# connector_schematic.net
KiCad netlist of a schematic drawn in EAGLE
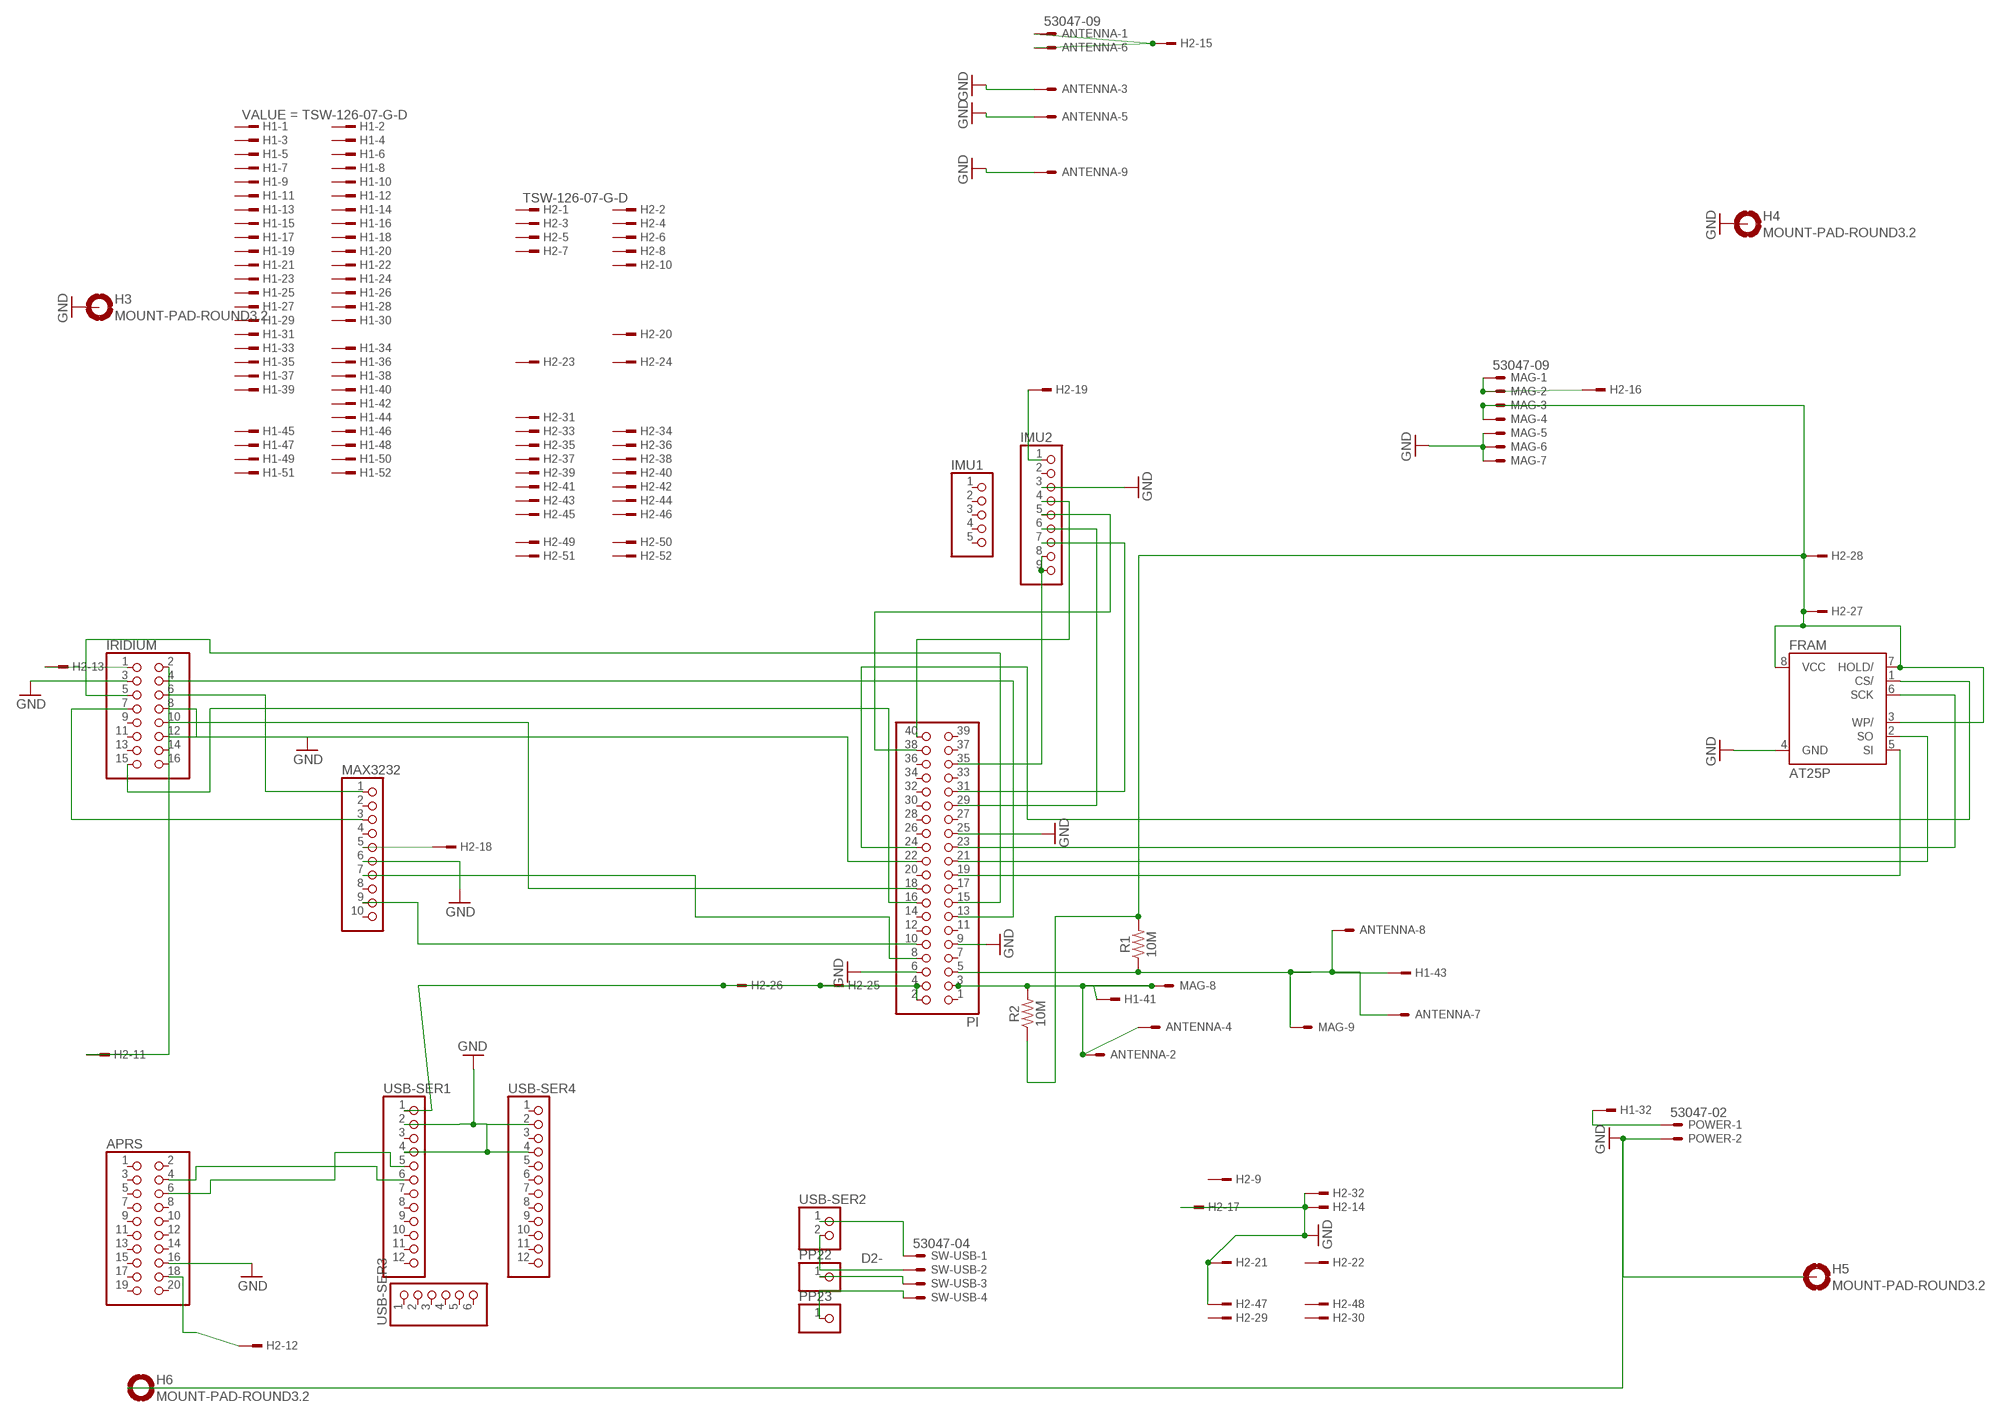
[diagram p0: schematic, sheet 1]

(export (version "E")
  (design (tool "Eeschema 10.0.6"))
  (components
    (comp (ref "ANTENNA")
      (value "53047-09")
      (footprint "eagle-import:53047-09")
      (fields (field (name "MF") "MOLEX") (field (name "MPN") "53047-0910"))
      (libsource (lib "eagle-import") (part "53?-09047"))
    )
    (comp (ref "APRS")
      (value "PINHD-2X10")
      (footprint "eagle-import:2X10")
      (libsource (lib "eagle-import") (part "PINHD-2X10"))
    )
    (comp (ref "FRAM")
      (value "AT25P")
      (footprint "eagle-import:DIL08")
      (fields (field (name "MPN") "CAT25040LI-G"))
      (libsource (lib "eagle-import") (part "AT25P"))
    )
    (comp (ref "H1")
      (value "TSW-126-07-G-D")
      (footprint "eagle-import:TSW-126-XX-G-D")
      (fields (field (name "MF") "Samtec Inc."))
      (libsource (lib "eagle-import") (part "TSW-126--G-D07"))
    )
    (comp (ref "H2")
      (value "TSW-126-07-G-D")
      (footprint "eagle-import:TSW-126-XX-G-D")
      (fields (field (name "MF") "Samtec Inc."))
      (libsource (lib "eagle-import") (part "TSW-126--G-D07"))
    )
    (comp (ref "H3")
      (value "MOUNT-PAD-ROUND3.2")
      (footprint "eagle-import:3,2-PAD")
      (libsource (lib "eagle-import") (part "MOUNT-PAD-ROUND3.2"))
    )
    (comp (ref "H4")
      (value "MOUNT-PAD-ROUND3.2")
      (footprint "eagle-import:3,2-PAD")
      (libsource (lib "eagle-import") (part "MOUNT-PAD-ROUND3.2"))
    )
    (comp (ref "H5")
      (value "MOUNT-PAD-ROUND3.2")
      (footprint "eagle-import:3,2-PAD")
      (libsource (lib "eagle-import") (part "MOUNT-PAD-ROUND3.2"))
    )
    (comp (ref "H6")
      (value "MOUNT-PAD-ROUND3.2")
      (footprint "eagle-import:3,2-PAD")
      (libsource (lib "eagle-import") (part "MOUNT-PAD-ROUND3.2"))
    )
    (comp (ref "IMU1")
      (value "PINHD-1X5")
      (footprint "eagle-import:1X05")
      (libsource (lib "eagle-import") (part "PINHD-1X5"))
    )
    (comp (ref "IMU2")
      (value "PINHD-1X9")
      (footprint "eagle-import:1X09")
      (libsource (lib "eagle-import") (part "PINHD-1X9"))
    )
    (comp (ref "IRIDIUM")
      (value "PINHD-2X8")
      (footprint "eagle-import:2X08")
      (libsource (lib "eagle-import") (part "PINHD-2X8"))
    )
    (comp (ref "MAG")
      (value "53047-09")
      (footprint "eagle-import:53047-09")
      (fields (field (name "MF") "MOLEX") (field (name "MPN") "53047-0910"))
      (libsource (lib "eagle-import") (part "53?-09047"))
    )
    (comp (ref "MAX3232")
      (value "PINHD-1X10")
      (footprint "eagle-import:1X10")
      (libsource (lib "eagle-import") (part "PINHD-1X10"))
    )
    (comp (ref "PI")
      (value "PINHD-2X20")
      (footprint "eagle-import:2X20")
      (libsource (lib "eagle-import") (part "PINHD-2X20"))
    )
    (comp (ref "POWER")
      (value "53047-02")
      (footprint "eagle-import:53047-02")
      (fields (field (name "MF") "MOLEX") (field (name "MPN") "53047-0210"))
      (libsource (lib "eagle-import") (part "53?-02047"))
    )
    (comp (ref "PP22")
      (value "PINHD-1X1")
      (footprint "eagle-import:1X01")
      (libsource (lib "eagle-import") (part "PINHD-1X1"))
    )
    (comp (ref "PP23")
      (value "PINHD-1X1")
      (footprint "eagle-import:1X01")
      (libsource (lib "eagle-import") (part "PINHD-1X1"))
    )
    (comp (ref "R1")
      (value "10M")
      (footprint "eagle-import:AXIAL-0.3")
      (libsource (lib "eagle-import") (part "10MOHM-HORIZ-1/4W-5%"))
    )
    (comp (ref "R2")
      (value "10M")
      (footprint "eagle-import:AXIAL-0.3")
      (libsource (lib "eagle-import") (part "10MOHM-HORIZ-1/4W-5%"))
    )
    (comp (ref "SW-USB")
      (value "53047-04")
      (footprint "eagle-import:53047-04")
      (fields (field (name "MF") "WALDOM/MOLEX") (field (name "MPN") "53047-0410"))
      (libsource (lib "eagle-import") (part "53?-04047"))
    )
    (comp (ref "USB-SER1")
      (value "PINHD-1X12")
      (footprint "eagle-import:1X12")
      (libsource (lib "eagle-import") (part "PINHD-1X12"))
    )
    (comp (ref "USB-SER2")
      (value "PINHD-1X2")
      (footprint "eagle-import:1X02")
      (libsource (lib "eagle-import") (part "PINHD-1X2"))
    )
    (comp (ref "USB-SER3")
      (value "PINHD-1X6")
      (footprint "eagle-import:1X06")
      (libsource (lib "eagle-import") (part "PINHD-1X6"))
    )
    (comp (ref "USB-SER4")
      (value "PINHD-1X12")
      (footprint "eagle-import:1X12")
      (libsource (lib "eagle-import") (part "PINHD-1X12"))
    )
  )
  (nets
    (net (code "1") (name "/D2-") (class "Default")
      (node (ref "SW-USB") (pin "2") (pinfunction "S_2") (pintype "passive"))
      (node (ref "USB-SER2") (pin "2") (pinfunction "2_2") (pintype "passive"))
    )
    (net (code "2") (name "GND") (class "Default")
      (node (ref "ANTENNA") (pin "3") (pinfunction "S_3") (pintype "passive"))
      (node (ref "ANTENNA") (pin "5") (pinfunction "S_5") (pintype "passive"))
      (node (ref "ANTENNA") (pin "9") (pinfunction "S_9") (pintype "passive"))
      (node (ref "APRS") (pin "16") (pinfunction "16_16") (pintype "passive"))
      (node (ref "FRAM") (pin "4") (pinfunction "GND_4") (pintype "power_in"))
      (node (ref "H2") (pin "14") (pinfunction "1_14") (pintype "passive"))
      (node (ref "H2") (pin "17") (pinfunction "1_17") (pintype "passive"))
      (node (ref "H2") (pin "21") (pinfunction "1_21") (pintype "passive"))
      (node (ref "H2") (pin "32") (pinfunction "1_32") (pintype "passive"))
      (node (ref "H2") (pin "47") (pinfunction "1_47") (pintype "passive"))
      (node (ref "H3") (pin "B3,2") (pinfunction "MOUNT_B3,2") (pintype "passive"))
      (node (ref "H4") (pin "B3,2") (pinfunction "MOUNT_B3,2") (pintype "passive"))
      (node (ref "H5") (pin "B3,2") (pinfunction "MOUNT_B3,2") (pintype "passive"))
      (node (ref "H6") (pin "B3,2") (pinfunction "MOUNT_B3,2") (pintype "passive"))
      (node (ref "IMU2") (pin "3") (pinfunction "3_3") (pintype "passive"))
      (node (ref "IRIDIUM") (pin "3") (pinfunction "3_3") (pintype "passive"))
      (node (ref "IRIDIUM") (pin "8") (pinfunction "8_8") (pintype "passive"))
      (node (ref "MAG") (pin "5") (pinfunction "S_5") (pintype "passive"))
      (node (ref "MAG") (pin "6") (pinfunction "S_6") (pintype "passive"))
      (node (ref "MAG") (pin "7") (pinfunction "S_7") (pintype "passive"))
      (node (ref "MAX3232") (pin "6") (pinfunction "6_6") (pintype "passive"))
      (node (ref "PI") (pin "25") (pinfunction "25_25") (pintype "passive"))
      (node (ref "PI") (pin "6") (pinfunction "6_6") (pintype "passive"))
      (node (ref "PI") (pin "9") (pinfunction "9_9") (pintype "passive"))
      (node (ref "POWER") (pin "2") (pinfunction "S_2") (pintype "passive"))
      (node (ref "USB-SER1") (pin "2") (pinfunction "2_2") (pintype "passive"))
      (node (ref "USB-SER1") (pin "4") (pinfunction "4_4") (pintype "passive"))
      (node (ref "USB-SER4") (pin "2") (pinfunction "2_2") (pintype "passive"))
      (node (ref "USB-SER4") (pin "4") (pinfunction "4_4") (pintype "passive"))
    )
    (net (code "3") (name "Net-(ANTENNAA-S)") (class "Default")
      (node (ref "ANTENNA") (pin "1") (pinfunction "S_1") (pintype "passive"))
      (node (ref "ANTENNA") (pin "6") (pinfunction "S_6") (pintype "passive"))
      (node (ref "H2") (pin "15") (pinfunction "1_15") (pintype "passive"))
    )
    (net (code "4") (name "Net-(ANTENNAB-S)") (class "Default")
      (node (ref "ANTENNA") (pin "2") (pinfunction "S_2") (pintype "passive"))
      (node (ref "ANTENNA") (pin "4") (pinfunction "S_4") (pintype "passive"))
      (node (ref "H1") (pin "41") (pinfunction "1_41") (pintype "passive"))
      (node (ref "MAG") (pin "8") (pinfunction "S_8") (pintype "passive"))
      (node (ref "PI") (pin "3") (pinfunction "3_3") (pintype "passive"))
      (node (ref "R2") (pin "P$2") (pinfunction "2_P$2") (pintype "passive"))
    )
    (net (code "5") (name "Net-(ANTENNAG-S)") (class "Default")
      (node (ref "ANTENNA") (pin "7") (pinfunction "S_7") (pintype "passive"))
      (node (ref "ANTENNA") (pin "8") (pinfunction "S_8") (pintype "passive"))
      (node (ref "H1") (pin "43") (pinfunction "1_43") (pintype "passive"))
      (node (ref "MAG") (pin "9") (pinfunction "S_9") (pintype "passive"))
      (node (ref "PI") (pin "5") (pinfunction "5_5") (pintype "passive"))
      (node (ref "R1") (pin "P$1") (pinfunction "1_P$1") (pintype "passive"))
    )
    (net (code "6") (name "Net-(APRS-Pad4)") (class "Default")
      (node (ref "APRS") (pin "4") (pinfunction "4_4") (pintype "passive"))
      (node (ref "USB-SER1") (pin "6") (pinfunction "6_6") (pintype "passive"))
    )
    (net (code "7") (name "Net-(APRS-Pad6)") (class "Default")
      (node (ref "APRS") (pin "6") (pinfunction "6_6") (pintype "passive"))
      (node (ref "USB-SER1") (pin "5") (pinfunction "5_5") (pintype "passive"))
    )
    (net (code "8") (name "Net-(FRAM-CS{slash})") (class "Default")
      (node (ref "FRAM") (pin "1") (pinfunction "CS/_1") (pintype "input"))
      (node (ref "PI") (pin "24") (pinfunction "24_24") (pintype "passive"))
    )
    (net (code "9") (name "Net-(FRAM-HOLD{slash})") (class "Default")
      (node (ref "FRAM") (pin "3") (pinfunction "WP/_3") (pintype "input"))
      (node (ref "FRAM") (pin "7") (pinfunction "HOLD/_7") (pintype "input"))
      (node (ref "FRAM") (pin "8") (pinfunction "VCC_8") (pintype "power_in"))
      (node (ref "H2") (pin "27") (pinfunction "1_27") (pintype "passive"))
      (node (ref "H2") (pin "28") (pinfunction "1_28") (pintype "passive"))
      (node (ref "MAG") (pin "3") (pinfunction "S_3") (pintype "passive"))
      (node (ref "MAG") (pin "4") (pinfunction "S_4") (pintype "passive"))
      (node (ref "R1") (pin "P$2") (pinfunction "2_P$2") (pintype "passive"))
      (node (ref "R2") (pin "P$1") (pinfunction "1_P$1") (pintype "passive"))
    )
    (net (code "10") (name "Net-(FRAM-SCK)") (class "Default")
      (node (ref "FRAM") (pin "6") (pinfunction "SCK_6") (pintype "bidirectional"))
      (node (ref "PI") (pin "23") (pinfunction "23_23") (pintype "passive"))
    )
    (net (code "11") (name "Net-(FRAM-SI)") (class "Default")
      (node (ref "FRAM") (pin "5") (pinfunction "SI_5") (pintype "bidirectional"))
      (node (ref "PI") (pin "19") (pinfunction "19_19") (pintype "passive"))
    )
    (net (code "12") (name "Net-(FRAM-SO)") (class "Default")
      (node (ref "FRAM") (pin "2") (pinfunction "SO_2") (pintype "input"))
      (node (ref "PI") (pin "21") (pinfunction "21_21") (pintype "passive"))
    )
    (net (code "13") (name "Net-(H1Z-1)") (class "Default")
      (node (ref "H1") (pin "32") (pinfunction "1_32") (pintype "passive"))
      (node (ref "POWER") (pin "1") (pinfunction "S_1") (pintype "passive"))
    )
    (net (code "14") (name "Net-(H2C-1)") (class "Default")
      (node (ref "H2") (pin "11") (pinfunction "1_11") (pintype "passive"))
      (node (ref "IRIDIUM") (pin "2") (pinfunction "2_2") (pintype "passive"))
    )
    (net (code "15") (name "Net-(H2D-1)") (class "Default")
      (node (ref "APRS") (pin "18") (pinfunction "18_18") (pintype "passive"))
      (node (ref "H2") (pin "12") (pinfunction "1_12") (pintype "passive"))
    )
    (net (code "16") (name "Net-(H2E-1)") (class "Default")
      (node (ref "H2") (pin "13") (pinfunction "1_13") (pintype "passive"))
      (node (ref "IRIDIUM") (pin "1") (pinfunction "1_1") (pintype "passive"))
    )
    (net (code "17") (name "Net-(H2H-1)") (class "Default")
      (node (ref "H2") (pin "16") (pinfunction "1_16") (pintype "passive"))
      (node (ref "MAG") (pin "1") (pinfunction "S_1") (pintype "passive"))
      (node (ref "MAG") (pin "2") (pinfunction "S_2") (pintype "passive"))
    )
    (net (code "18") (name "Net-(H2J-1)") (class "Default")
      (node (ref "H2") (pin "18") (pinfunction "1_18") (pintype "passive"))
      (node (ref "MAX3232") (pin "5") (pinfunction "5_5") (pintype "passive"))
    )
    (net (code "19") (name "Net-(H2K-1)") (class "Default")
      (node (ref "H2") (pin "19") (pinfunction "1_19") (pintype "passive"))
      (node (ref "IMU2") (pin "1") (pinfunction "1_1") (pintype "passive"))
    )
    (net (code "20") (name "Net-(H2R-1)") (class "Default")
      (node (ref "H2") (pin "25") (pinfunction "1_25") (pintype "passive"))
      (node (ref "H2") (pin "26") (pinfunction "1_26") (pintype "passive"))
      (node (ref "PI") (pin "2") (pinfunction "2_2") (pintype "passive"))
      (node (ref "PI") (pin "4") (pinfunction "4_4") (pintype "passive"))
      (node (ref "USB-SER1") (pin "1") (pinfunction "1_1") (pintype "passive"))
    )
    (net (code "21") (name "Net-(IMU2-Pad4)") (class "Default")
      (node (ref "IMU2") (pin "4") (pinfunction "4_4") (pintype "passive"))
      (node (ref "PI") (pin "40") (pinfunction "40_40") (pintype "passive"))
    )
    (net (code "22") (name "Net-(IMU2-Pad5)") (class "Default")
      (node (ref "IMU2") (pin "5") (pinfunction "5_5") (pintype "passive"))
      (node (ref "PI") (pin "38") (pinfunction "38_38") (pintype "passive"))
    )
    (net (code "23") (name "Net-(IMU2-Pad6)") (class "Default")
      (node (ref "IMU2") (pin "6") (pinfunction "6_6") (pintype "passive"))
      (node (ref "PI") (pin "29") (pinfunction "29_29") (pintype "passive"))
    )
    (net (code "24") (name "Net-(IMU2-Pad7)") (class "Default")
      (node (ref "IMU2") (pin "7") (pinfunction "7_7") (pintype "passive"))
      (node (ref "PI") (pin "31") (pinfunction "31_31") (pintype "passive"))
    )
    (net (code "25") (name "Net-(IMU2-Pad8)") (class "Default")
      (node (ref "IMU2") (pin "8") (pinfunction "8_8") (pintype "passive"))
      (node (ref "IMU2") (pin "9") (pinfunction "9_9") (pintype "passive"))
      (node (ref "PI") (pin "35") (pinfunction "35_35") (pintype "passive"))
    )
    (net (code "26") (name "Net-(IRIDIUM-Pad4)") (class "Default")
      (node (ref "IRIDIUM") (pin "4") (pinfunction "4_4") (pintype "passive"))
      (node (ref "PI") (pin "13") (pinfunction "13_13") (pintype "passive"))
    )
    (net (code "27") (name "Net-(IRIDIUM-Pad5)") (class "Default")
      (node (ref "IRIDIUM") (pin "5") (pinfunction "5_5") (pintype "passive"))
      (node (ref "PI") (pin "15") (pinfunction "15_15") (pintype "passive"))
    )
    (net (code "28") (name "Net-(IRIDIUM-Pad6)") (class "Default")
      (node (ref "IRIDIUM") (pin "6") (pinfunction "6_6") (pintype "passive"))
      (node (ref "MAX3232") (pin "1") (pinfunction "1_1") (pintype "passive"))
    )
    (net (code "29") (name "Net-(IRIDIUM-Pad7)") (class "Default")
      (node (ref "IRIDIUM") (pin "7") (pinfunction "7_7") (pintype "passive"))
      (node (ref "MAX3232") (pin "3") (pinfunction "3_3") (pintype "passive"))
    )
    (net (code "30") (name "Net-(IRIDIUM-Pad10)") (class "Default")
      (node (ref "IRIDIUM") (pin "10") (pinfunction "10_10") (pintype "passive"))
      (node (ref "PI") (pin "18") (pinfunction "18_18") (pintype "passive"))
    )
    (net (code "31") (name "Net-(IRIDIUM-Pad12)") (class "Default")
      (node (ref "IRIDIUM") (pin "12") (pinfunction "12_12") (pintype "passive"))
      (node (ref "PI") (pin "22") (pinfunction "22_22") (pintype "passive"))
    )
    (net (code "32") (name "Net-(IRIDIUM-Pad15)") (class "Default")
      (node (ref "IRIDIUM") (pin "15") (pinfunction "15_15") (pintype "passive"))
      (node (ref "PI") (pin "16") (pinfunction "16_16") (pintype "passive"))
    )
    (net (code "33") (name "Net-(MAX3232-Pad7)") (class "Default")
      (node (ref "MAX3232") (pin "7") (pinfunction "7_7") (pintype "passive"))
      (node (ref "PI") (pin "8") (pinfunction "8_8") (pintype "passive"))
    )
    (net (code "34") (name "Net-(MAX3232-Pad9)") (class "Default")
      (node (ref "MAX3232") (pin "9") (pinfunction "9_9") (pintype "passive"))
      (node (ref "PI") (pin "10") (pinfunction "10_10") (pintype "passive"))
    )
    (net (code "35") (name "Net-(SW-USBA-S)") (class "Default")
      (node (ref "SW-USB") (pin "1") (pinfunction "S_1") (pintype "passive"))
      (node (ref "USB-SER2") (pin "1") (pinfunction "1_1") (pintype "passive"))
    )
    (net (code "36") (name "Net-(SW-USBC-S)") (class "Default")
      (node (ref "PP22") (pin "1") (pinfunction "1_1") (pintype "passive"))
      (node (ref "SW-USB") (pin "3") (pinfunction "S_3") (pintype "passive"))
    )
    (net (code "37") (name "Net-(SW-USBD-S)") (class "Default")
      (node (ref "PP23") (pin "1") (pinfunction "1_1") (pintype "passive"))
      (node (ref "SW-USB") (pin "4") (pinfunction "S_4") (pintype "passive"))
    )
    (net (code "38") (name "unconnected-(APRS-Pad1)") (class "Default")
      (node (ref "APRS") (pin "1") (pinfunction "1_1") (pintype "passive"))
    )
    (net (code "39") (name "unconnected-(APRS-Pad2)") (class "Default")
      (node (ref "APRS") (pin "2") (pinfunction "2_2") (pintype "passive"))
    )
    (net (code "40") (name "unconnected-(APRS-Pad3)") (class "Default")
      (node (ref "APRS") (pin "3") (pinfunction "3_3") (pintype "passive"))
    )
    (net (code "41") (name "unconnected-(APRS-Pad5)") (class "Default")
      (node (ref "APRS") (pin "5") (pinfunction "5_5") (pintype "passive"))
    )
    (net (code "42") (name "unconnected-(APRS-Pad7)") (class "Default")
      (node (ref "APRS") (pin "7") (pinfunction "7_7") (pintype "passive"))
    )
    (net (code "43") (name "unconnected-(APRS-Pad8)") (class "Default")
      (node (ref "APRS") (pin "8") (pinfunction "8_8") (pintype "passive"))
    )
    (net (code "44") (name "unconnected-(APRS-Pad9)") (class "Default")
      (node (ref "APRS") (pin "9") (pinfunction "9_9") (pintype "passive"))
    )
    (net (code "45") (name "unconnected-(APRS-Pad10)") (class "Default")
      (node (ref "APRS") (pin "10") (pinfunction "10_10") (pintype "passive"))
    )
    (net (code "46") (name "unconnected-(APRS-Pad11)") (class "Default")
      (node (ref "APRS") (pin "11") (pinfunction "11_11") (pintype "passive"))
    )
    (net (code "47") (name "unconnected-(APRS-Pad12)") (class "Default")
      (node (ref "APRS") (pin "12") (pinfunction "12_12") (pintype "passive"))
    )
    (net (code "48") (name "unconnected-(APRS-Pad13)") (class "Default")
      (node (ref "APRS") (pin "13") (pinfunction "13_13") (pintype "passive"))
    )
    (net (code "49") (name "unconnected-(APRS-Pad14)") (class "Default")
      (node (ref "APRS") (pin "14") (pinfunction "14_14") (pintype "passive"))
    )
    (net (code "50") (name "unconnected-(APRS-Pad15)") (class "Default")
      (node (ref "APRS") (pin "15") (pinfunction "15_15") (pintype "passive"))
    )
    (net (code "51") (name "unconnected-(APRS-Pad17)") (class "Default")
      (node (ref "APRS") (pin "17") (pinfunction "17_17") (pintype "passive"))
    )
    (net (code "52") (name "unconnected-(APRS-Pad19)") (class "Default")
      (node (ref "APRS") (pin "19") (pinfunction "19_19") (pintype "passive"))
    )
    (net (code "53") (name "unconnected-(APRS-Pad20)") (class "Default")
      (node (ref "APRS") (pin "20") (pinfunction "20_20") (pintype "passive"))
    )
    (net (code "54") (name "unconnected-(H1-Pad1)") (class "Default")
      (node (ref "H1") (pin "1") (pinfunction "1_1") (pintype "passive"))
    )
    (net (code "55") (name "unconnected-(H1AA-1-Pad33)") (class "Default")
      (node (ref "H1") (pin "33") (pinfunction "1_33") (pintype "passive"))
    )
    (net (code "56") (name "unconnected-(H1AB-1-Pad34)") (class "Default")
      (node (ref "H1") (pin "34") (pinfunction "1_34") (pintype "passive"))
    )
    (net (code "57") (name "unconnected-(H1AC-1-Pad35)") (class "Default")
      (node (ref "H1") (pin "35") (pinfunction "1_35") (pintype "passive"))
    )
    (net (code "58") (name "unconnected-(H1AD-1-Pad36)") (class "Default")
      (node (ref "H1") (pin "36") (pinfunction "1_36") (pintype "passive"))
    )
    (net (code "59") (name "unconnected-(H1AE-1-Pad37)") (class "Default")
      (node (ref "H1") (pin "37") (pinfunction "1_37") (pintype "passive"))
    )
    (net (code "60") (name "unconnected-(H1AF-1-Pad38)") (class "Default")
      (node (ref "H1") (pin "38") (pinfunction "1_38") (pintype "passive"))
    )
    (net (code "61") (name "unconnected-(H1AG-1-Pad39)") (class "Default")
      (node (ref "H1") (pin "39") (pinfunction "1_39") (pintype "passive"))
    )
    (net (code "62") (name "unconnected-(H1AH-1-Pad4)") (class "Default")
      (node (ref "H1") (pin "4") (pinfunction "1_4") (pintype "passive"))
    )
    (net (code "63") (name "unconnected-(H1AI-1-Pad40)") (class "Default")
      (node (ref "H1") (pin "40") (pinfunction "1_40") (pintype "passive"))
    )
    (net (code "64") (name "unconnected-(H1AK-1-Pad42)") (class "Default")
      (node (ref "H1") (pin "42") (pinfunction "1_42") (pintype "passive"))
    )
    (net (code "65") (name "unconnected-(H1AM-1-Pad44)") (class "Default")
      (node (ref "H1") (pin "44") (pinfunction "1_44") (pintype "passive"))
    )
    (net (code "66") (name "unconnected-(H1AN-1-Pad45)") (class "Default")
      (node (ref "H1") (pin "45") (pinfunction "1_45") (pintype "passive"))
    )
    (net (code "67") (name "unconnected-(H1AO-1-Pad46)") (class "Default")
      (node (ref "H1") (pin "46") (pinfunction "1_46") (pintype "passive"))
    )
    (net (code "68") (name "unconnected-(H1AP-1-Pad47)") (class "Default")
      (node (ref "H1") (pin "47") (pinfunction "1_47") (pintype "passive"))
    )
    (net (code "69") (name "unconnected-(H1AQ-1-Pad48)") (class "Default")
      (node (ref "H1") (pin "48") (pinfunction "1_48") (pintype "passive"))
    )
    (net (code "70") (name "unconnected-(H1AR-1-Pad49)") (class "Default")
      (node (ref "H1") (pin "49") (pinfunction "1_49") (pintype "passive"))
    )
    (net (code "71") (name "unconnected-(H1AS-1-Pad5)") (class "Default")
      (node (ref "H1") (pin "5") (pinfunction "1_5") (pintype "passive"))
    )
    (net (code "72") (name "unconnected-(H1AT-1-Pad50)") (class "Default")
      (node (ref "H1") (pin "50") (pinfunction "1_50") (pintype "passive"))
    )
    (net (code "73") (name "unconnected-(H1AU-1-Pad51)") (class "Default")
      (node (ref "H1") (pin "51") (pinfunction "1_51") (pintype "passive"))
    )
    (net (code "74") (name "unconnected-(H1AV-1-Pad52)") (class "Default")
      (node (ref "H1") (pin "52") (pinfunction "1_52") (pintype "passive"))
    )
    (net (code "75") (name "unconnected-(H1AW-1-Pad6)") (class "Default")
      (node (ref "H1") (pin "6") (pinfunction "1_6") (pintype "passive"))
    )
    (net (code "76") (name "unconnected-(H1AX-1-Pad7)") (class "Default")
      (node (ref "H1") (pin "7") (pinfunction "1_7") (pintype "passive"))
    )
    (net (code "77") (name "unconnected-(H1AY-1-Pad8)") (class "Default")
      (node (ref "H1") (pin "8") (pinfunction "1_8") (pintype "passive"))
    )
    (net (code "78") (name "unconnected-(H1AZ-1-Pad9)") (class "Default")
      (node (ref "H1") (pin "9") (pinfunction "1_9") (pintype "passive"))
    )
    (net (code "79") (name "unconnected-(H1B-1-Pad10)") (class "Default")
      (node (ref "H1") (pin "10") (pinfunction "1_10") (pintype "passive"))
    )
    (net (code "80") (name "unconnected-(H1C-1-Pad11)") (class "Default")
      (node (ref "H1") (pin "11") (pinfunction "1_11") (pintype "passive"))
    )
    (net (code "81") (name "unconnected-(H1D-1-Pad12)") (class "Default")
      (node (ref "H1") (pin "12") (pinfunction "1_12") (pintype "passive"))
    )
    (net (code "82") (name "unconnected-(H1E-1-Pad13)") (class "Default")
      (node (ref "H1") (pin "13") (pinfunction "1_13") (pintype "passive"))
    )
    (net (code "83") (name "unconnected-(H1F-1-Pad14)") (class "Default")
      (node (ref "H1") (pin "14") (pinfunction "1_14") (pintype "passive"))
    )
    (net (code "84") (name "unconnected-(H1G-1-Pad15)") (class "Default")
      (node (ref "H1") (pin "15") (pinfunction "1_15") (pintype "passive"))
    )
    (net (code "85") (name "unconnected-(H1H-1-Pad16)") (class "Default")
      (node (ref "H1") (pin "16") (pinfunction "1_16") (pintype "passive"))
    )
    (net (code "86") (name "unconnected-(H1I-1-Pad17)") (class "Default")
      (node (ref "H1") (pin "17") (pinfunction "1_17") (pintype "passive"))
    )
    (net (code "87") (name "unconnected-(H1J-1-Pad18)") (class "Default")
      (node (ref "H1") (pin "18") (pinfunction "1_18") (pintype "passive"))
    )
    (net (code "88") (name "unconnected-(H1K-1-Pad19)") (class "Default")
      (node (ref "H1") (pin "19") (pinfunction "1_19") (pintype "passive"))
    )
    (net (code "89") (name "unconnected-(H1L-1-Pad2)") (class "Default")
      (node (ref "H1") (pin "2") (pinfunction "1_2") (pintype "passive"))
    )
    (net (code "90") (name "unconnected-(H1M-1-Pad20)") (class "Default")
      (node (ref "H1") (pin "20") (pinfunction "1_20") (pintype "passive"))
    )
    (net (code "91") (name "unconnected-(H1N-1-Pad21)") (class "Default")
      (node (ref "H1") (pin "21") (pinfunction "1_21") (pintype "passive"))
    )
    (net (code "92") (name "unconnected-(H1O-1-Pad22)") (class "Default")
      (node (ref "H1") (pin "22") (pinfunction "1_22") (pintype "passive"))
    )
    (net (code "93") (name "unconnected-(H1P-1-Pad23)") (class "Default")
      (node (ref "H1") (pin "23") (pinfunction "1_23") (pintype "passive"))
    )
    (net (code "94") (name "unconnected-(H1Q-1-Pad24)") (class "Default")
      (node (ref "H1") (pin "24") (pinfunction "1_24") (pintype "passive"))
    )
    (net (code "95") (name "unconnected-(H1R-1-Pad25)") (class "Default")
      (node (ref "H1") (pin "25") (pinfunction "1_25") (pintype "passive"))
    )
    (net (code "96") (name "unconnected-(H1S-1-Pad26)") (class "Default")
      (node (ref "H1") (pin "26") (pinfunction "1_26") (pintype "passive"))
    )
    (net (code "97") (name "unconnected-(H1T-1-Pad27)") (class "Default")
      (node (ref "H1") (pin "27") (pinfunction "1_27") (pintype "passive"))
    )
    (net (code "98") (name "unconnected-(H1U-1-Pad28)") (class "Default")
      (node (ref "H1") (pin "28") (pinfunction "1_28") (pintype "passive"))
    )
    (net (code "99") (name "unconnected-(H1V-1-Pad29)") (class "Default")
      (node (ref "H1") (pin "29") (pinfunction "1_29") (pintype "passive"))
    )
    (net (code "100") (name "unconnected-(H1W-1-Pad3)") (class "Default")
      (node (ref "H1") (pin "3") (pinfunction "1_3") (pintype "passive"))
    )
    (net (code "101") (name "unconnected-(H1X-1-Pad30)") (class "Default")
      (node (ref "H1") (pin "30") (pinfunction "1_30") (pintype "passive"))
    )
    (net (code "102") (name "unconnected-(H1Y-1-Pad31)") (class "Default")
      (node (ref "H1") (pin "31") (pinfunction "1_31") (pintype "passive"))
    )
    (net (code "103") (name "unconnected-(H2-Pad1)") (class "Default")
      (node (ref "H2") (pin "1") (pinfunction "1_1") (pintype "passive"))
    )
    (net (code "104") (name "unconnected-(H2AA-1-Pad33)") (class "Default")
      (node (ref "H2") (pin "33") (pinfunction "1_33") (pintype "passive"))
    )
    (net (code "105") (name "unconnected-(H2AB-1-Pad34)") (class "Default")
      (node (ref "H2") (pin "34") (pinfunction "1_34") (pintype "passive"))
    )
    (net (code "106") (name "unconnected-(H2AC-1-Pad35)") (class "Default")
      (node (ref "H2") (pin "35") (pinfunction "1_35") (pintype "passive"))
    )
    (net (code "107") (name "unconnected-(H2AD-1-Pad36)") (class "Default")
      (node (ref "H2") (pin "36") (pinfunction "1_36") (pintype "passive"))
    )
    (net (code "108") (name "unconnected-(H2AE-1-Pad37)") (class "Default")
      (node (ref "H2") (pin "37") (pinfunction "1_37") (pintype "passive"))
    )
    (net (code "109") (name "unconnected-(H2AF-1-Pad38)") (class "Default")
      (node (ref "H2") (pin "38") (pinfunction "1_38") (pintype "passive"))
    )
    (net (code "110") (name "unconnected-(H2AG-1-Pad39)") (class "Default")
      (node (ref "H2") (pin "39") (pinfunction "1_39") (pintype "passive"))
    )
    (net (code "111") (name "unconnected-(H2AH-1-Pad4)") (class "Default")
      (node (ref "H2") (pin "4") (pinfunction "1_4") (pintype "passive"))
    )
    (net (code "112") (name "unconnected-(H2AI-1-Pad40)") (class "Default")
      (node (ref "H2") (pin "40") (pinfunction "1_40") (pintype "passive"))
    )
    (net (code "113") (name "unconnected-(H2AJ-1-Pad41)") (class "Default")
      (node (ref "H2") (pin "41") (pinfunction "1_41") (pintype "passive"))
    )
    (net (code "114") (name "unconnected-(H2AK-1-Pad42)") (class "Default")
      (node (ref "H2") (pin "42") (pinfunction "1_42") (pintype "passive"))
    )
    (net (code "115") (name "unconnected-(H2AL-1-Pad43)") (class "Default")
      (node (ref "H2") (pin "43") (pinfunction "1_43") (pintype "passive"))
    )
    (net (code "116") (name "unconnected-(H2AM-1-Pad44)") (class "Default")
      (node (ref "H2") (pin "44") (pinfunction "1_44") (pintype "passive"))
    )
    (net (code "117") (name "unconnected-(H2AN-1-Pad45)") (class "Default")
      (node (ref "H2") (pin "45") (pinfunction "1_45") (pintype "passive"))
    )
    (net (code "118") (name "unconnected-(H2AO-1-Pad46)") (class "Default")
      (node (ref "H2") (pin "46") (pinfunction "1_46") (pintype "passive"))
    )
    (net (code "119") (name "unconnected-(H2AQ-1-Pad48)") (class "Default")
      (node (ref "H2") (pin "48") (pinfunction "1_48") (pintype "passive"))
    )
    (net (code "120") (name "unconnected-(H2AR-1-Pad49)") (class "Default")
      (node (ref "H2") (pin "49") (pinfunction "1_49") (pintype "passive"))
    )
    (net (code "121") (name "unconnected-(H2AS-1-Pad5)") (class "Default")
      (node (ref "H2") (pin "5") (pinfunction "1_5") (pintype "passive"))
    )
    (net (code "122") (name "unconnected-(H2AT-1-Pad50)") (class "Default")
      (node (ref "H2") (pin "50") (pinfunction "1_50") (pintype "passive"))
    )
    (net (code "123") (name "unconnected-(H2AU-1-Pad51)") (class "Default")
      (node (ref "H2") (pin "51") (pinfunction "1_51") (pintype "passive"))
    )
    (net (code "124") (name "unconnected-(H2AV-1-Pad52)") (class "Default")
      (node (ref "H2") (pin "52") (pinfunction "1_52") (pintype "passive"))
    )
    (net (code "125") (name "unconnected-(H2AW-1-Pad6)") (class "Default")
      (node (ref "H2") (pin "6") (pinfunction "1_6") (pintype "passive"))
    )
    (net (code "126") (name "unconnected-(H2AX-1-Pad7)") (class "Default")
      (node (ref "H2") (pin "7") (pinfunction "1_7") (pintype "passive"))
    )
    (net (code "127") (name "unconnected-(H2AY-1-Pad8)") (class "Default")
      (node (ref "H2") (pin "8") (pinfunction "1_8") (pintype "passive"))
    )
    (net (code "128") (name "unconnected-(H2AZ-1-Pad9)") (class "Default")
      (node (ref "H2") (pin "9") (pinfunction "1_9") (pintype "passive"))
    )
    (net (code "129") (name "unconnected-(H2B-1-Pad10)") (class "Default")
      (node (ref "H2") (pin "10") (pinfunction "1_10") (pintype "passive"))
    )
    (net (code "130") (name "unconnected-(H2L-1-Pad2)") (class "Default")
      (node (ref "H2") (pin "2") (pinfunction "1_2") (pintype "passive"))
    )
    (net (code "131") (name "unconnected-(H2M-1-Pad20)") (class "Default")
      (node (ref "H2") (pin "20") (pinfunction "1_20") (pintype "passive"))
    )
    (net (code "132") (name "unconnected-(H2O-1-Pad22)") (class "Default")
      (node (ref "H2") (pin "22") (pinfunction "1_22") (pintype "passive"))
    )
    (net (code "133") (name "unconnected-(H2P-1-Pad23)") (class "Default")
      (node (ref "H2") (pin "23") (pinfunction "1_23") (pintype "passive"))
    )
    (net (code "134") (name "unconnected-(H2Q-1-Pad24)") (class "Default")
      (node (ref "H2") (pin "24") (pinfunction "1_24") (pintype "passive"))
    )
    (net (code "135") (name "unconnected-(H2V-1-Pad29)") (class "Default")
      (node (ref "H2") (pin "29") (pinfunction "1_29") (pintype "passive"))
    )
    (net (code "136") (name "unconnected-(H2W-1-Pad3)") (class "Default")
      (node (ref "H2") (pin "3") (pinfunction "1_3") (pintype "passive"))
    )
    (net (code "137") (name "unconnected-(H2X-1-Pad30)") (class "Default")
      (node (ref "H2") (pin "30") (pinfunction "1_30") (pintype "passive"))
    )
    (net (code "138") (name "unconnected-(H2Y-1-Pad31)") (class "Default")
      (node (ref "H2") (pin "31") (pinfunction "1_31") (pintype "passive"))
    )
    (net (code "139") (name "unconnected-(IMU1-Pad1)") (class "Default")
      (node (ref "IMU1") (pin "1") (pinfunction "1_1") (pintype "passive"))
    )
    (net (code "140") (name "unconnected-(IMU1-Pad2)") (class "Default")
      (node (ref "IMU1") (pin "2") (pinfunction "2_2") (pintype "passive"))
    )
    (net (code "141") (name "unconnected-(IMU1-Pad3)") (class "Default")
      (node (ref "IMU1") (pin "3") (pinfunction "3_3") (pintype "passive"))
    )
    (net (code "142") (name "unconnected-(IMU1-Pad4)") (class "Default")
      (node (ref "IMU1") (pin "4") (pinfunction "4_4") (pintype "passive"))
    )
    (net (code "143") (name "unconnected-(IMU1-Pad5)") (class "Default")
      (node (ref "IMU1") (pin "5") (pinfunction "5_5") (pintype "passive"))
    )
    (net (code "144") (name "unconnected-(IMU2-Pad2)") (class "Default")
      (node (ref "IMU2") (pin "2") (pinfunction "2_2") (pintype "passive"))
    )
    (net (code "145") (name "unconnected-(IRIDIUM-Pad9)") (class "Default")
      (node (ref "IRIDIUM") (pin "9") (pinfunction "9_9") (pintype "passive"))
    )
    (net (code "146") (name "unconnected-(IRIDIUM-Pad11)") (class "Default")
      (node (ref "IRIDIUM") (pin "11") (pinfunction "11_11") (pintype "passive"))
    )
    (net (code "147") (name "unconnected-(IRIDIUM-Pad13)") (class "Default")
      (node (ref "IRIDIUM") (pin "13") (pinfunction "13_13") (pintype "passive"))
    )
    (net (code "148") (name "unconnected-(IRIDIUM-Pad14)") (class "Default")
      (node (ref "IRIDIUM") (pin "14") (pinfunction "14_14") (pintype "passive"))
    )
    (net (code "149") (name "unconnected-(IRIDIUM-Pad16)") (class "Default")
      (node (ref "IRIDIUM") (pin "16") (pinfunction "16_16") (pintype "passive"))
    )
    (net (code "150") (name "unconnected-(MAX3232-Pad2)") (class "Default")
      (node (ref "MAX3232") (pin "2") (pinfunction "2_2") (pintype "passive"))
    )
    (net (code "151") (name "unconnected-(MAX3232-Pad4)") (class "Default")
      (node (ref "MAX3232") (pin "4") (pinfunction "4_4") (pintype "passive"))
    )
    (net (code "152") (name "unconnected-(MAX3232-Pad8)") (class "Default")
      (node (ref "MAX3232") (pin "8") (pinfunction "8_8") (pintype "passive"))
    )
    (net (code "153") (name "unconnected-(MAX3232-Pad10)") (class "Default")
      (node (ref "MAX3232") (pin "10") (pinfunction "10_10") (pintype "passive"))
    )
    (net (code "154") (name "unconnected-(PI-Pad1)") (class "Default")
      (node (ref "PI") (pin "1") (pinfunction "1_1") (pintype "passive"))
    )
    (net (code "155") (name "unconnected-(PI-Pad7)") (class "Default")
      (node (ref "PI") (pin "7") (pinfunction "7_7") (pintype "passive"))
    )
    (net (code "156") (name "unconnected-(PI-Pad11)") (class "Default")
      (node (ref "PI") (pin "11") (pinfunction "11_11") (pintype "passive"))
    )
    (net (code "157") (name "unconnected-(PI-Pad12)") (class "Default")
      (node (ref "PI") (pin "12") (pinfunction "12_12") (pintype "passive"))
    )
    (net (code "158") (name "unconnected-(PI-Pad14)") (class "Default")
      (node (ref "PI") (pin "14") (pinfunction "14_14") (pintype "passive"))
    )
    (net (code "159") (name "unconnected-(PI-Pad17)") (class "Default")
      (node (ref "PI") (pin "17") (pinfunction "17_17") (pintype "passive"))
    )
    (net (code "160") (name "unconnected-(PI-Pad20)") (class "Default")
      (node (ref "PI") (pin "20") (pinfunction "20_20") (pintype "passive"))
    )
    (net (code "161") (name "unconnected-(PI-Pad26)") (class "Default")
      (node (ref "PI") (pin "26") (pinfunction "26_26") (pintype "passive"))
    )
    (net (code "162") (name "unconnected-(PI-Pad27)") (class "Default")
      (node (ref "PI") (pin "27") (pinfunction "27_27") (pintype "passive"))
    )
    (net (code "163") (name "unconnected-(PI-Pad28)") (class "Default")
      (node (ref "PI") (pin "28") (pinfunction "28_28") (pintype "passive"))
    )
    (net (code "164") (name "unconnected-(PI-Pad30)") (class "Default")
      (node (ref "PI") (pin "30") (pinfunction "30_30") (pintype "passive"))
    )
    (net (code "165") (name "unconnected-(PI-Pad32)") (class "Default")
      (node (ref "PI") (pin "32") (pinfunction "32_32") (pintype "passive"))
    )
    (net (code "166") (name "unconnected-(PI-Pad33)") (class "Default")
      (node (ref "PI") (pin "33") (pinfunction "33_33") (pintype "passive"))
    )
    (net (code "167") (name "unconnected-(PI-Pad34)") (class "Default")
      (node (ref "PI") (pin "34") (pinfunction "34_34") (pintype "passive"))
    )
    (net (code "168") (name "unconnected-(PI-Pad36)") (class "Default")
      (node (ref "PI") (pin "36") (pinfunction "36_36") (pintype "passive"))
    )
    (net (code "169") (name "unconnected-(PI-Pad37)") (class "Default")
      (node (ref "PI") (pin "37") (pinfunction "37_37") (pintype "passive"))
    )
    (net (code "170") (name "unconnected-(PI-Pad39)") (class "Default")
      (node (ref "PI") (pin "39") (pinfunction "39_39") (pintype "passive"))
    )
    (net (code "171") (name "unconnected-(USB-SER1-Pad3)") (class "Default")
      (node (ref "USB-SER1") (pin "3") (pinfunction "3_3") (pintype "passive"))
    )
    (net (code "172") (name "unconnected-(USB-SER1-Pad7)") (class "Default")
      (node (ref "USB-SER1") (pin "7") (pinfunction "7_7") (pintype "passive"))
    )
    (net (code "173") (name "unconnected-(USB-SER1-Pad8)") (class "Default")
      (node (ref "USB-SER1") (pin "8") (pinfunction "8_8") (pintype "passive"))
    )
    (net (code "174") (name "unconnected-(USB-SER1-Pad9)") (class "Default")
      (node (ref "USB-SER1") (pin "9") (pinfunction "9_9") (pintype "passive"))
    )
    (net (code "175") (name "unconnected-(USB-SER1-Pad10)") (class "Default")
      (node (ref "USB-SER1") (pin "10") (pinfunction "10_10") (pintype "passive"))
    )
    (net (code "176") (name "unconnected-(USB-SER1-Pad11)") (class "Default")
      (node (ref "USB-SER1") (pin "11") (pinfunction "11_11") (pintype "passive"))
    )
    (net (code "177") (name "unconnected-(USB-SER1-Pad12)") (class "Default")
      (node (ref "USB-SER1") (pin "12") (pinfunction "12_12") (pintype "passive"))
    )
    (net (code "178") (name "unconnected-(USB-SER3-Pad1)") (class "Default")
      (node (ref "USB-SER3") (pin "1") (pinfunction "1_1") (pintype "passive"))
    )
    (net (code "179") (name "unconnected-(USB-SER3-Pad2)") (class "Default")
      (node (ref "USB-SER3") (pin "2") (pinfunction "2_2") (pintype "passive"))
    )
    (net (code "180") (name "unconnected-(USB-SER3-Pad3)") (class "Default")
      (node (ref "USB-SER3") (pin "3") (pinfunction "3_3") (pintype "passive"))
    )
    (net (code "181") (name "unconnected-(USB-SER3-Pad4)") (class "Default")
      (node (ref "USB-SER3") (pin "4") (pinfunction "4_4") (pintype "passive"))
    )
    (net (code "182") (name "unconnected-(USB-SER3-Pad5)") (class "Default")
      (node (ref "USB-SER3") (pin "5") (pinfunction "5_5") (pintype "passive"))
    )
    (net (code "183") (name "unconnected-(USB-SER3-Pad6)") (class "Default")
      (node (ref "USB-SER3") (pin "6") (pinfunction "6_6") (pintype "passive"))
    )
    (net (code "184") (name "unconnected-(USB-SER4-Pad1)") (class "Default")
      (node (ref "USB-SER4") (pin "1") (pinfunction "1_1") (pintype "passive"))
    )
    (net (code "185") (name "unconnected-(USB-SER4-Pad3)") (class "Default")
      (node (ref "USB-SER4") (pin "3") (pinfunction "3_3") (pintype "passive"))
    )
    (net (code "186") (name "unconnected-(USB-SER4-Pad5)") (class "Default")
      (node (ref "USB-SER4") (pin "5") (pinfunction "5_5") (pintype "passive"))
    )
    (net (code "187") (name "unconnected-(USB-SER4-Pad6)") (class "Default")
      (node (ref "USB-SER4") (pin "6") (pinfunction "6_6") (pintype "passive"))
    )
    (net (code "188") (name "unconnected-(USB-SER4-Pad7)") (class "Default")
      (node (ref "USB-SER4") (pin "7") (pinfunction "7_7") (pintype "passive"))
    )
    (net (code "189") (name "unconnected-(USB-SER4-Pad8)") (class "Default")
      (node (ref "USB-SER4") (pin "8") (pinfunction "8_8") (pintype "passive"))
    )
    (net (code "190") (name "unconnected-(USB-SER4-Pad9)") (class "Default")
      (node (ref "USB-SER4") (pin "9") (pinfunction "9_9") (pintype "passive"))
    )
    (net (code "191") (name "unconnected-(USB-SER4-Pad10)") (class "Default")
      (node (ref "USB-SER4") (pin "10") (pinfunction "10_10") (pintype "passive"))
    )
    (net (code "192") (name "unconnected-(USB-SER4-Pad11)") (class "Default")
      (node (ref "USB-SER4") (pin "11") (pinfunction "11_11") (pintype "passive"))
    )
    (net (code "193") (name "unconnected-(USB-SER4-Pad12)") (class "Default")
      (node (ref "USB-SER4") (pin "12") (pinfunction "12_12") (pintype "passive"))
    )
  )
)
